# input1.net
KiCad netlist of a schematic drawn in Altium Designer
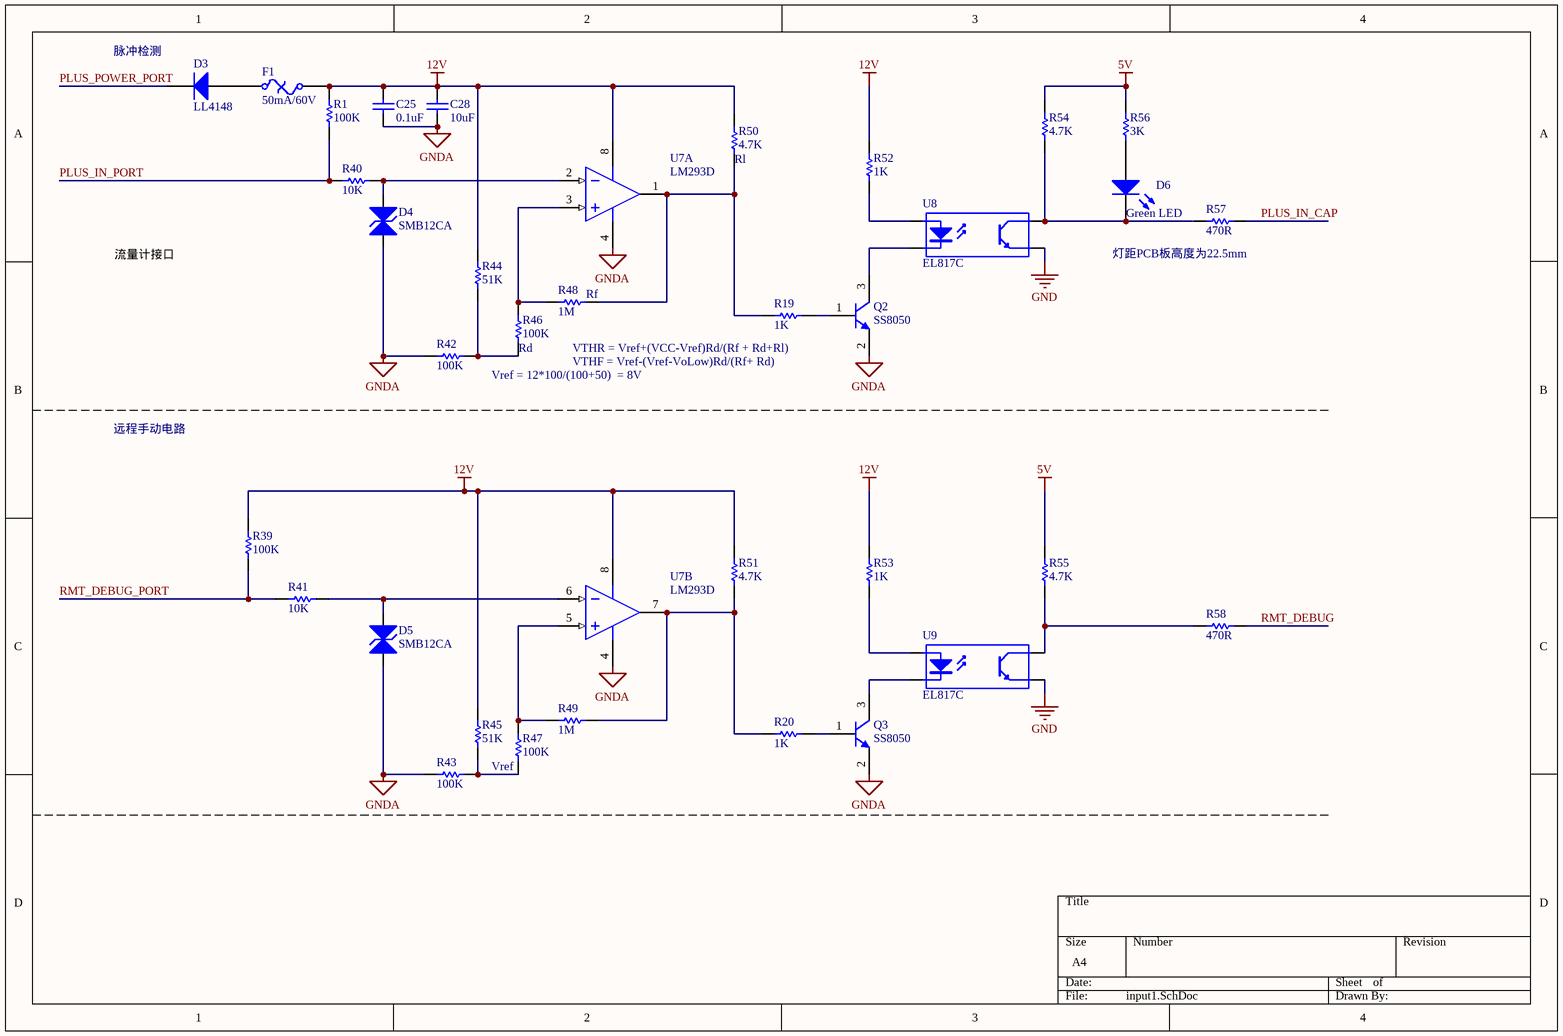
[diagram p0: input1.SchDoc]

(export (version "E")
  (design (tool "Eeschema 10.0.6"))
  (components
    (comp (ref "C25")
      (value "0.1uF")
      (footprint "CAPC2012M")
      (description "Capacitor")
      (fields (field (name "PUBLISHER") "Altium Limited"))
      (libsource (lib "Miscellaneous Devices") (part "Cap"))
    )
    (comp (ref "C28")
      (value "10uF")
      (footprint "CAPC2012M")
      (description "Capacitor")
      (fields (field (name "PUBLISHER") "Altium Limited"))
      (libsource (lib "Miscellaneous Devices") (part "Cap"))
    )
    (comp (ref "D3")
      (value "LL4148")
      (footprint "CD3216-1206")
      (description "1 Amp General Purpose Rectifier")
      (fields (field (name "PUBLISHER") "Altium Limited"))
      (libsource (lib "Miscellaneous Devices") (part "Diode 1N4007"))
    )
    (comp (ref "D4")
      (value "SMB12CA")
      (footprint "SMB")
      (description "Bi-dir TVS Diode")
      (fields (field (name "PUBLISHER") "Altium Limited"))
      (libsource (lib "UserLib") (part "Bi-dir TVS Diode"))
    )
    (comp (ref "D5")
      (value "SMB12CA")
      (footprint "SMB")
      (description "Bi-dir TVS Diode")
      (fields (field (name "PUBLISHER") "Altium Limited"))
      (libsource (lib "UserLib") (part "Bi-dir TVS Diode"))
    )
    (comp (ref "D6")
      (value "Green LED")
      (footprint "LED254A")
      (description "Green LED ,SIP, Dia =3mm")
      (fields (field (name "PUBLISHER") "Altium Limited"))
      (libsource (lib "Miscellaneous Devices") (part "LED1"))
    )
    (comp (ref "F1")
      (value "50mA/60V")
      (footprint "RESC3216M")
      (description "Thermal Fuse")
      (fields (field (name "PUBLISHER") "Altium Limited"))
      (libsource (lib "Miscellaneous Devices") (part "Fuse Thermal"))
    )
    (comp (ref "Q2")
      (value "SS8050")
      (footprint "SOT-23_N")
      (description "NPN BISS Transistor")
      (fields (field (name "PUBLISHER") "Altium Limited"))
      (libsource (lib "Philips Discrete BJT - Low Power") (part "PMMT491A"))
    )
    (comp (ref "Q3")
      (value "SS8050")
      (footprint "SOT-23_N")
      (description "NPN BISS Transistor")
      (fields (field (name "PUBLISHER") "Altium Limited"))
      (libsource (lib "Philips Discrete BJT - Low Power") (part "PMMT491A"))
    )
    (comp (ref "R1")
      (value "100K")
      (footprint "RESC2012M")
      (description "Resistor")
      (fields (field (name "PUBLISHER") "Altium Limited"))
      (libsource (lib "Miscellaneous Devices") (part "Res1"))
    )
    (comp (ref "R19")
      (value "1K")
      (footprint "RESC2012M")
      (description "Resistor")
      (fields (field (name "PUBLISHER") "Altium Limited"))
      (libsource (lib "Miscellaneous Devices") (part "Res1"))
    )
    (comp (ref "R20")
      (value "1K")
      (footprint "RESC2012M")
      (description "Resistor")
      (fields (field (name "PUBLISHER") "Altium Limited"))
      (libsource (lib "Miscellaneous Devices") (part "Res1"))
    )
    (comp (ref "R39")
      (value "100K")
      (footprint "RESC2012M")
      (description "Resistor")
      (fields (field (name "PUBLISHER") "Altium Limited"))
      (libsource (lib "Miscellaneous Devices") (part "Res1"))
    )
    (comp (ref "R40")
      (value "10K")
      (footprint "RESC2012M")
      (description "Resistor")
      (fields (field (name "PUBLISHER") "Altium Limited"))
      (libsource (lib "Miscellaneous Devices") (part "Res1"))
    )
    (comp (ref "R41")
      (value "10K")
      (footprint "RESC2012M")
      (description "Resistor")
      (fields (field (name "PUBLISHER") "Altium Limited"))
      (libsource (lib "Miscellaneous Devices") (part "Res1"))
    )
    (comp (ref "R42")
      (value "100K")
      (footprint "RESC2012M")
      (description "Resistor")
      (fields (field (name "PUBLISHER") "Altium Limited"))
      (libsource (lib "Miscellaneous Devices") (part "Res1"))
    )
    (comp (ref "R43")
      (value "100K")
      (footprint "RESC2012M")
      (description "Resistor")
      (fields (field (name "PUBLISHER") "Altium Limited"))
      (libsource (lib "Miscellaneous Devices") (part "Res1"))
    )
    (comp (ref "R44")
      (value "51K")
      (footprint "RESC2012M")
      (description "Resistor")
      (fields (field (name "PUBLISHER") "Altium Limited"))
      (libsource (lib "Miscellaneous Devices") (part "Res1"))
    )
    (comp (ref "R45")
      (value "51K")
      (footprint "RESC2012M")
      (description "Resistor")
      (fields (field (name "PUBLISHER") "Altium Limited"))
      (libsource (lib "Miscellaneous Devices") (part "Res1"))
    )
    (comp (ref "R46")
      (value "100K")
      (footprint "RESC2012M")
      (description "Resistor")
      (fields (field (name "PUBLISHER") "Altium Limited"))
      (libsource (lib "Miscellaneous Devices") (part "Res1"))
    )
    (comp (ref "R47")
      (value "100K")
      (footprint "RESC2012M")
      (description "Resistor")
      (fields (field (name "PUBLISHER") "Altium Limited"))
      (libsource (lib "Miscellaneous Devices") (part "Res1"))
    )
    (comp (ref "R48")
      (value "1M")
      (footprint "RESC2012M")
      (description "Resistor")
      (fields (field (name "PUBLISHER") "Altium Limited"))
      (libsource (lib "Miscellaneous Devices") (part "Res1"))
    )
    (comp (ref "R49")
      (value "1M")
      (footprint "RESC2012M")
      (description "Resistor")
      (fields (field (name "PUBLISHER") "Altium Limited"))
      (libsource (lib "Miscellaneous Devices") (part "Res1"))
    )
    (comp (ref "R50")
      (value "4.7K")
      (footprint "RESC2012M")
      (description "Resistor")
      (fields (field (name "PUBLISHER") "Altium Limited"))
      (libsource (lib "Miscellaneous Devices") (part "Res1"))
    )
    (comp (ref "R51")
      (value "4.7K")
      (footprint "RESC2012M")
      (description "Resistor")
      (fields (field (name "PUBLISHER") "Altium Limited"))
      (libsource (lib "Miscellaneous Devices") (part "Res1"))
    )
    (comp (ref "R52")
      (value "1K")
      (footprint "RESC2012M")
      (description "Resistor")
      (fields (field (name "PUBLISHER") "Altium Limited"))
      (libsource (lib "Miscellaneous Devices") (part "Res1"))
    )
    (comp (ref "R53")
      (value "1K")
      (footprint "RESC2012M")
      (description "Resistor")
      (fields (field (name "PUBLISHER") "Altium Limited"))
      (libsource (lib "Miscellaneous Devices") (part "Res1"))
    )
    (comp (ref "R54")
      (value "4.7K")
      (footprint "RESC2012M")
      (description "Resistor")
      (fields (field (name "PUBLISHER") "Altium Limited"))
      (libsource (lib "Miscellaneous Devices") (part "Res1"))
    )
    (comp (ref "R55")
      (value "4.7K")
      (footprint "RESC2012M")
      (description "Resistor")
      (fields (field (name "PUBLISHER") "Altium Limited"))
      (libsource (lib "Miscellaneous Devices") (part "Res1"))
    )
    (comp (ref "R56")
      (value "3K")
      (footprint "RESC2012M")
      (description "Resistor")
      (fields (field (name "PUBLISHER") "Altium Limited"))
      (libsource (lib "Miscellaneous Devices") (part "Res1"))
    )
    (comp (ref "R57")
      (value "470R")
      (footprint "RESC2012M")
      (description "Resistor")
      (fields (field (name "PUBLISHER") "Altium Limited"))
      (libsource (lib "Miscellaneous Devices") (part "Res1"))
    )
    (comp (ref "R58")
      (value "470R")
      (footprint "RESC2012M")
      (description "Resistor")
      (fields (field (name "PUBLISHER") "Altium Limited"))
      (libsource (lib "Miscellaneous Devices") (part "Res1"))
    )
    (comp (ref "U7")
      (value "LM293D")
      (footprint "SO8_N")
      (description "Low-Power Dual Voltage Comparator")
      (fields (field (name "PUBLISHER") "Altium Limited"))
      (libsource (lib "ST Analog Comparator") (part "LM393AD"))
    )
    (comp (ref "U8")
      (value "EL817C")
      (footprint "SO-4LA")
      (description "4-Pin Phototransistor Optocoupler")
      (fields (field (name "PUBLISHER") "Altium Limited"))
      (libsource (lib "Miscellaneous Devices") (part "Optoisolator1"))
    )
    (comp (ref "U9")
      (value "EL817C")
      (footprint "SO-4LA")
      (description "4-Pin Phototransistor Optocoupler")
      (fields (field (name "PUBLISHER") "Altium Limited"))
      (libsource (lib "Miscellaneous Devices") (part "Optoisolator1"))
    )
  )
  (nets
    (net (code "1") (name "/PLUS_IN_CAP") (class "Default")
      (node (ref "R57") (pin "2") (pinfunction "2_2") (pintype "passive"))
    )
    (net (code "2") (name "/PLUS_IN_PORT") (class "Default")
      (node (ref "R1") (pin "1") (pinfunction "1_1") (pintype "passive"))
      (node (ref "R40") (pin "2") (pinfunction "2_2") (pintype "passive"))
    )
    (net (code "3") (name "/PLUS_POWER_PORT") (class "Default")
      (node (ref "D3") (pin "2") (pinfunction "K_2") (pintype "passive"))
    )
    (net (code "4") (name "/RMT_DEBUG") (class "Default")
      (node (ref "R58") (pin "2") (pinfunction "2_2") (pintype "passive"))
    )
    (net (code "5") (name "/RMT_DEBUG_PORT") (class "Default")
      (node (ref "R39") (pin "1") (pinfunction "1_1") (pintype "passive"))
      (node (ref "R41") (pin "2") (pinfunction "2_2") (pintype "passive"))
    )
    (net (code "6") (name "5V") (class "Default")
      (node (ref "R54") (pin "2") (pinfunction "2_2") (pintype "passive"))
      (node (ref "R55") (pin "2") (pinfunction "2_2") (pintype "passive"))
      (node (ref "R56") (pin "1") (pinfunction "1_1") (pintype "passive"))
    )
    (net (code "7") (name "12V") (class "Default")
      (node (ref "C25") (pin "2") (pinfunction "2_2") (pintype "passive"))
      (node (ref "C28") (pin "2") (pinfunction "2_2") (pintype "passive"))
      (node (ref "F1") (pin "2") (pinfunction "2_2") (pintype "passive"))
      (node (ref "R1") (pin "2") (pinfunction "2_2") (pintype "passive"))
      (node (ref "R39") (pin "2") (pinfunction "2_2") (pintype "passive"))
      (node (ref "R44") (pin "2") (pinfunction "2_2") (pintype "passive"))
      (node (ref "R45") (pin "2") (pinfunction "2_2") (pintype "passive"))
      (node (ref "R50") (pin "1") (pinfunction "1_1") (pintype "passive"))
      (node (ref "R51") (pin "2") (pinfunction "2_2") (pintype "passive"))
      (node (ref "R52") (pin "1") (pinfunction "1_1") (pintype "passive"))
      (node (ref "R53") (pin "1") (pinfunction "1_1") (pintype "passive"))
      (node (ref "U7") (pin "8") (pinfunction "V+_8") (pintype "power_in"))
    )
    (net (code "8") (name "GND") (class "Default")
      (node (ref "U8") (pin "3") (pinfunction "E_3") (pintype "passive"))
      (node (ref "U9") (pin "3") (pinfunction "E_3") (pintype "passive"))
    )
    (net (code "9") (name "GNDA") (class "Default")
      (node (ref "C25") (pin "1") (pinfunction "1_1") (pintype "passive"))
      (node (ref "C28") (pin "1") (pinfunction "1_1") (pintype "passive"))
      (node (ref "D4") (pin "1") (pinfunction "A_1") (pintype "passive"))
      (node (ref "D5") (pin "1") (pinfunction "A_1") (pintype "passive"))
      (node (ref "Q2") (pin "2") (pinfunction "E_2") (pintype "passive"))
      (node (ref "Q3") (pin "2") (pinfunction "E_2") (pintype "passive"))
      (node (ref "R42") (pin "1") (pinfunction "1_1") (pintype "passive"))
      (node (ref "R43") (pin "1") (pinfunction "1_1") (pintype "passive"))
      (node (ref "U7") (pin "4") (pinfunction "V-_4") (pintype "power_in"))
    )
    (net (code "10") (name "Net-(D3-A)") (class "Default")
      (node (ref "D3") (pin "1") (pinfunction "A_1") (pintype "passive"))
      (node (ref "F1") (pin "1") (pinfunction "1_1") (pintype "passive"))
    )
    (net (code "11") (name "Net-(D4-K)") (class "Default")
      (node (ref "D4") (pin "2") (pinfunction "K_2") (pintype "passive"))
      (node (ref "R40") (pin "1") (pinfunction "1_1") (pintype "passive"))
      (node (ref "U7") (pin "2") (pinfunction "IN-_2") (pintype "input"))
    )
    (net (code "12") (name "Net-(D5-K)") (class "Default")
      (node (ref "D5") (pin "2") (pinfunction "K_2") (pintype "passive"))
      (node (ref "R41") (pin "1") (pinfunction "1_1") (pintype "passive"))
      (node (ref "U7") (pin "6") (pinfunction "IN-_6") (pintype "input"))
    )
    (net (code "13") (name "Net-(D6-A)") (class "Default")
      (node (ref "D6") (pin "1") (pinfunction "A_1") (pintype "passive"))
      (node (ref "R56") (pin "2") (pinfunction "2_2") (pintype "passive"))
    )
    (net (code "14") (name "Net-(D6-K)") (class "Default")
      (node (ref "D6") (pin "2") (pinfunction "K_2") (pintype "passive"))
      (node (ref "R54") (pin "1") (pinfunction "1_1") (pintype "passive"))
      (node (ref "R57") (pin "1") (pinfunction "1_1") (pintype "passive"))
      (node (ref "U8") (pin "4") (pinfunction "C_4") (pintype "passive"))
    )
    (net (code "15") (name "Net-(Q2-B)") (class "Default")
      (node (ref "Q2") (pin "1") (pinfunction "B_1") (pintype "passive"))
      (node (ref "R19") (pin "2") (pinfunction "2_2") (pintype "passive"))
    )
    (net (code "16") (name "Net-(Q2-C)") (class "Default")
      (node (ref "Q2") (pin "3") (pinfunction "C_3") (pintype "passive"))
      (node (ref "U8") (pin "2") (pinfunction "K_2") (pintype "passive"))
    )
    (net (code "17") (name "Net-(Q3-B)") (class "Default")
      (node (ref "Q3") (pin "1") (pinfunction "B_1") (pintype "passive"))
      (node (ref "R20") (pin "2") (pinfunction "2_2") (pintype "passive"))
    )
    (net (code "18") (name "Net-(Q3-C)") (class "Default")
      (node (ref "Q3") (pin "3") (pinfunction "C_3") (pintype "passive"))
      (node (ref "U9") (pin "2") (pinfunction "K_2") (pintype "passive"))
    )
    (net (code "19") (name "Net-(R42-Pad2)") (class "Default")
      (node (ref "R42") (pin "2") (pinfunction "2_2") (pintype "passive"))
      (node (ref "R44") (pin "1") (pinfunction "1_1") (pintype "passive"))
      (node (ref "R46") (pin "1") (pinfunction "1_1") (pintype "passive"))
    )
    (net (code "20") (name "Net-(R43-Pad2)") (class "Default")
      (node (ref "R43") (pin "2") (pinfunction "2_2") (pintype "passive"))
      (node (ref "R45") (pin "1") (pinfunction "1_1") (pintype "passive"))
      (node (ref "R47") (pin "1") (pinfunction "1_1") (pintype "passive"))
    )
    (net (code "21") (name "Net-(U7A-IN+)") (class "Default")
      (node (ref "R46") (pin "2") (pinfunction "2_2") (pintype "passive"))
      (node (ref "R48") (pin "2") (pinfunction "2_2") (pintype "passive"))
      (node (ref "U7") (pin "3") (pinfunction "IN+_3") (pintype "input"))
    )
    (net (code "22") (name "Net-(U7A-OUT)") (class "Default")
      (node (ref "R19") (pin "1") (pinfunction "1_1") (pintype "passive"))
      (node (ref "R48") (pin "1") (pinfunction "1_1") (pintype "passive"))
      (node (ref "R50") (pin "2") (pinfunction "2_2") (pintype "passive"))
      (node (ref "U7") (pin "1") (pinfunction "OUT_1") (pintype "open_collector"))
    )
    (net (code "23") (name "Net-(U7B-IN+)") (class "Default")
      (node (ref "R47") (pin "2") (pinfunction "2_2") (pintype "passive"))
      (node (ref "R49") (pin "1") (pinfunction "1_1") (pintype "passive"))
      (node (ref "U7") (pin "5") (pinfunction "IN+_5") (pintype "input"))
    )
    (net (code "24") (name "Net-(U7B-OUT)") (class "Default")
      (node (ref "R20") (pin "1") (pinfunction "1_1") (pintype "passive"))
      (node (ref "R49") (pin "2") (pinfunction "2_2") (pintype "passive"))
      (node (ref "R51") (pin "1") (pinfunction "1_1") (pintype "passive"))
      (node (ref "U7") (pin "7") (pinfunction "OUT_7") (pintype "open_collector"))
    )
    (net (code "25") (name "Net-(U8-A)") (class "Default")
      (node (ref "R52") (pin "2") (pinfunction "2_2") (pintype "passive"))
      (node (ref "U8") (pin "1") (pinfunction "A_1") (pintype "passive"))
    )
    (net (code "26") (name "Net-(U9-A)") (class "Default")
      (node (ref "R53") (pin "2") (pinfunction "2_2") (pintype "passive"))
      (node (ref "U9") (pin "1") (pinfunction "A_1") (pintype "passive"))
    )
    (net (code "27") (name "Net-(U9-C)") (class "Default")
      (node (ref "R55") (pin "1") (pinfunction "1_1") (pintype "passive"))
      (node (ref "R58") (pin "1") (pinfunction "1_1") (pintype "passive"))
      (node (ref "U9") (pin "4") (pinfunction "C_4") (pintype "passive"))
    )
  )
)
